# SBH_MCU.net
KiCad netlist of a schematic drawn in Altium Designer
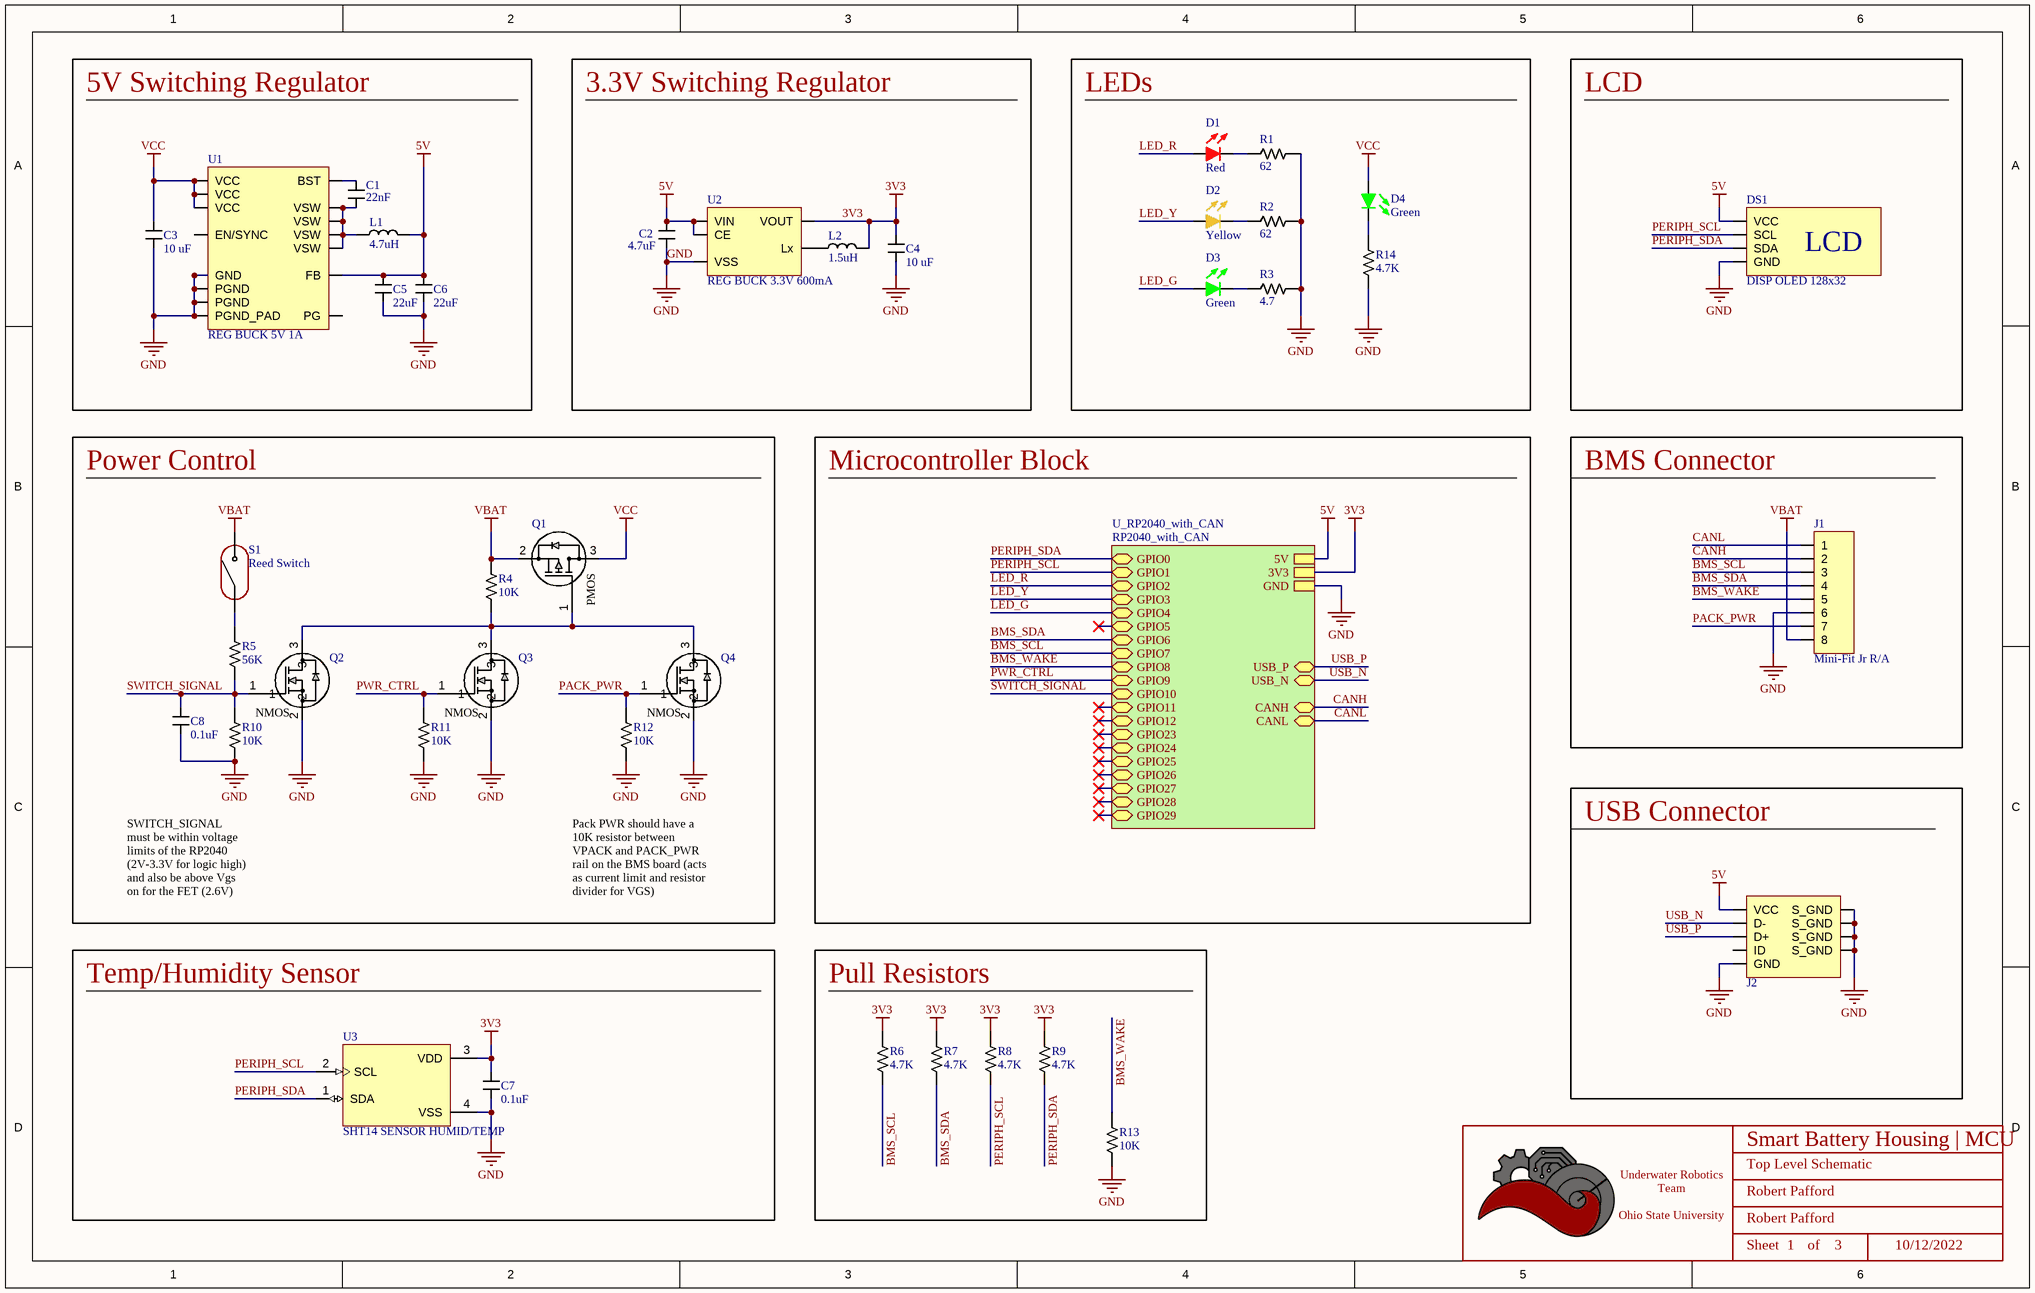
[diagram p0: SBH_MCU.SchDoc]

(export (version "E")
  (design (tool "Eeschema 10.0.6"))
  (components
    (comp (ref "*")
      (value "Title_Block")
      (footprint "LOGO")
      (description "UWRT Schematic Title Block Template\r\n\r\nCreated June 2021, Dylan Trainor")
      (libsource (lib "UWRT") (part "Title_Block"))
    )
    (comp (ref "C1")
      (value "22nF")
      (footprint "CAPACITOR_0402")
      (description "Cap 22nF 25V +/-10%\r\nCeramic 0402")
      (fields
        (field (name "TOLERANCE") "+/- 10%")
        (field (name "VOLTAGE") "25V")
        (field (name "MADE BY") "Robert Pafford")
      )
      (libsource (lib "Capacitors") (part "CAPACITOR_0.022uF_0402"))
    )
    (comp (ref "C2")
      (value "4.7uF")
      (footprint "CAPACITOR_0603")
      (description "Cap 4.7uF 6.3V +/-10%\r\nCeramic 0603")
      (fields
        (field (name "TOLERANCE") "+/- 10%")
        (field (name "VOLTAGE") "6.3V")
        (field (name "MADE BY") "Robert Pafford")
      )
      (libsource (lib "Capacitors") (part "CAPACITOR_4.7uF_0603"))
    )
    (comp (ref "C3")
      (value "10uF Ceramic 25V")
      (footprint "CAPACITOR_1206")
      (description "Cap 10uF 25V +/-10%\r\nCeramic 1206")
      (fields
        (field (name "TOLERANCE") "+/- 10%")
        (field (name "VOLTAGE") "25V")
        (field (name "VALUE (UF)") "10 uF")
        (field (name "MADE BY") "Robert Pafford")
      )
      (libsource (lib "Capacitors") (part "CAPACITOR_10uF_1206"))
    )
    (comp (ref "C4")
      (value "10uF Ceramic 6.3V")
      (footprint "CAPACITOR_0603")
      (description "Cap 10uF 6.3V +/-20%\r\nCeramic 0603")
      (fields
        (field (name "TOLERANCE") "+/- 20%")
        (field (name "VOLTAGE") "6.3V")
        (field (name "VALUE (UF)") "10 uF")
        (field (name "MADE BY") "Flip B")
      )
      (libsource (lib "Capacitors") (part "CAPACITOR_10uF_0603"))
    )
    (comp (ref "C5")
      (value "22uF")
      (footprint "CAPACITOR_0805")
      (description "Cap 22uF 10V +/-20% X5R\r\nCeramic 0805")
      (fields
        (field (name "TOLERANCE") "+/- 20%")
        (field (name "VOLTAGE") "10V")
        (field (name "MADE BY") "Robert Pafford")
      )
      (libsource (lib "Capacitors") (part "CAPACITOR_22uF_0805"))
    )
    (comp (ref "C6")
      (value "22uF")
      (footprint "CAPACITOR_0805")
      (description "Cap 22uF 10V +/-20% X5R\r\nCeramic 0805")
      (fields
        (field (name "TOLERANCE") "+/- 20%")
        (field (name "VOLTAGE") "10V")
        (field (name "MADE BY") "Robert Pafford")
      )
      (libsource (lib "Capacitors") (part "CAPACITOR_22uF_0805"))
    )
    (comp (ref "C7")
      (value "0.1uF")
      (footprint "CAPACITOR_0402")
      (description "Cap 100nF 25V +/-10%\r\nCeramic 0402")
      (fields
        (field (name "TOLERANCE") "+/- 10%")
        (field (name "VOLTAGE") "25V")
        (field (name "MADE BY") "Robert Pafford")
      )
      (libsource (lib "Capacitors") (part "CAPACITOR_0.1uF_0402"))
    )
    (comp (ref "C8")
      (value "0.1uF")
      (footprint "CAPACITOR_0402")
      (description "Cap 100nF 25V +/-10%\r\nCeramic 0402")
      (fields
        (field (name "TOLERANCE") "+/- 10%")
        (field (name "VOLTAGE") "25V")
        (field (name "MADE BY") "Robert Pafford")
      )
      (libsource (lib "Capacitors") (part "CAPACITOR_0.1uF_0402"))
    )
    (comp (ref "D1")
      (value "150060RS75000")
      (footprint "LED_0603")
      (description "LED Red Vf= 2V If = 0.020A\r\n150060RS75000")
      (fields (field (name "COLOR") "Red") (field (name "MADE BY") "Robert Pafford"))
      (libsource (lib "Diodes") (part "LED_Red_0603"))
    )
    (comp (ref "D2")
      (value "150060YS75000")
      (footprint "LED_0603")
      (description "LED Yellow Vf= 2V If = 0.020A\r\n150060YS75000")
      (fields (field (name "COLOR") "Yellow") (field (name "MADE BY") "Robert Pafford"))
      (libsource (lib "Diodes") (part "LED_Yellow_0603"))
    )
    (comp (ref "D3")
      (value "150060GS75000")
      (footprint "LED_0603")
      (description "LED Green Vf= 3.2V If = 0.025A\r\n150060GS75000")
      (fields (field (name "COLOR") "Green") (field (name "MADE BY") "Flip B"))
      (libsource (lib "Diodes") (part "LED_Green_0603_3.2V"))
    )
    (comp (ref "D4")
      (value "150060GS75000")
      (footprint "LED_0603")
      (description "LED Green Vf= 3.2V If = 0.025A\r\n150060GS75000")
      (fields (field (name "COLOR") "Green") (field (name "MADE BY") "Flip B"))
      (libsource (lib "Diodes") (part "LED_Green_0603_3.2V"))
    )
    (comp (ref "DS1")
      (value "DISP OLED 128x32")
      (footprint "OLED_I2C_128x32")
      (description "0.91'' 128x32 I2C OLED LCD Display Module")
      (fields (field (name "MADE BY") "Robert Pafford"))
      (libsource (lib "Modules") (part "OLED_I2C_128x32"))
    )
    (comp (ref "J1")
      (value "Mini-Fit Jr R/A")
      (footprint "Molex_Mili-Grid_2x4PIN_2.00MM_RA")
      (description "Molex Mili-Grid 2.00mm pitch 8 Pos Right Angle")
      (fields (field (name "MANUFACTURER") "Molex") (field (name "CREATED BY") "Flip B"))
      (libsource (lib "Connectors") (part "CONN_MOLEX_MiliGrid_8POS_R/A"))
    )
    (comp (ref "J2")
      (value "USB_MICRO R/A")
      (footprint "CONN_MINIUSB")
      (description "Amphenol Micro USB-B\r\nUSB2.0 5 Pin Right Angle SMD")
      (fields (field (name "MANUFACTURER") "Amphenol") (field (name "CREATED BY") "Flip B"))
      (libsource (lib "Connectors") (part "CONN_MICROUSB"))
    )
    (comp (ref "L1")
      (value "4.7uH")
      (footprint "INDUCTOR_SLF7045")
      (description "4.7 µH Shielded Drum Core, Wirewound Inductor 2.1 A 36mOhm Max Nonstandard")
      (fields
        (field (name "TOLERANCE") "+/- 20%")
        (field (name "Comment") "4.7uH Shielded Drum Core")
        (field (name "MADE BY") "Robert Pafford")
      )
      (libsource (lib "Inductors") (part "INDUCTOR_4.7uH_SLF7045T"))
    )
    (comp (ref "L2")
      (value "1.5uH")
      (footprint "INDUCTOR_NR3015")
      (description "Inductor Shielded 1.5uH 1.8A +/-30%")
      (fields
        (field (name "TOLERANCE") "+/- 30%")
        (field (name "Comment") "1.5uH Shielded")
        (field (name "MADE BY") "Robert Pafford")
      )
      (libsource (lib "Inductors") (part "INDUCTOR_1.5uH_NR3015"))
    )
    (comp (ref "Q1")
      (value "DMP3056L-7")
      (footprint "SOT-23-3")
      (description "P-Channel 30V 4.3A (Ta) 1.38W (Ta) Surface Mount SOT23")
      (fields (field (name "CREATED BY") "John Ulm") (field (name "REVIEWED BY") "---"))
      (libsource (lib "Transistors") (part "DMP3056L-7"))
    )
    (comp (ref "Q2")
      (value "MOSFET N-CH 30V 5.8A SOT-23-3")
      (footprint "SOT-23-3")
      (description "N-Channel 30 V 5.8A (Ta) 1.4W (Ta) Surface Mount SOT-23-3")
      (fields (field (name "MANUFACTURER _PART_NUMBER") "AO3404A") (field (name "CREATED BY") "Dylan T"))
      (libsource (lib "Transistors") (part "AO3404A"))
    )
    (comp (ref "Q3")
      (value "MOSFET N-CH 30V 5.8A SOT-23-3")
      (footprint "SOT-23-3")
      (description "N-Channel 30 V 5.8A (Ta) 1.4W (Ta) Surface Mount SOT-23-3")
      (fields (field (name "MANUFACTURER _PART_NUMBER") "AO3404A") (field (name "CREATED BY") "Dylan T"))
      (libsource (lib "Transistors") (part "AO3404A"))
    )
    (comp (ref "Q4")
      (value "MOSFET N-CH 30V 5.8A SOT-23-3")
      (footprint "SOT-23-3")
      (description "N-Channel 30 V 5.8A (Ta) 1.4W (Ta) Surface Mount SOT-23-3")
      (fields (field (name "MANUFACTURER _PART_NUMBER") "AO3404A") (field (name "CREATED BY") "Dylan T"))
      (libsource (lib "Transistors") (part "AO3404A"))
    )
    (comp (ref "R1")
      (value "62 Ohm 1% 1/4W")
      (footprint "RESISTOR_0603")
      (description "RES SMD 62 OHM 1% 1/4W 0603")
      (fields
        (field (name "TOLERANCE") "+/- 1%")
        (field (name "VALUE  (OHMS)") "62")
        (field (name "MADE BY") "Robert Pafford")
      )
      (libsource (lib "Resistors") (part "RESISTOR_62_0603"))
    )
    (comp (ref "R2")
      (value "62 Ohm 1% 1/4W")
      (footprint "RESISTOR_0603")
      (description "RES SMD 62 OHM 1% 1/4W 0603")
      (fields
        (field (name "TOLERANCE") "+/- 1%")
        (field (name "VALUE  (OHMS)") "62")
        (field (name "MADE BY") "Robert Pafford")
      )
      (libsource (lib "Resistors") (part "RESISTOR_62_0603"))
    )
    (comp (ref "R3")
      (value "4.7 Ohm 5% 1/8W")
      (footprint "RESISTOR_0603")
      (description "RES 4.7 OHM 5% 1/8W 0603")
      (fields
        (field (name "TOLERANCE") "+/- 5%")
        (field (name "VALUE  (OHMS)") "4.7")
        (field (name "MADE BY") "Robert Pafford")
      )
      (libsource (lib "Resistors") (part "RESISTOR_4.7_0603"))
    )
    (comp (ref "R4")
      (value "10k Ohm 5% 1/10W")
      (footprint "RESISTOR_0603")
      (description "RES 10k OHM 5% 1/10W 0603")
      (fields
        (field (name "TOLERANCE") "+/- 5%")
        (field (name "VALUE  (OHMS)") "10K")
        (field (name "MADE BY") "Robert Pafford")
      )
      (libsource (lib "Resistors") (part "RESISTOR_10K_0603"))
    )
    (comp (ref "R5")
      (value "56k Ohm 1% 1/16W")
      (footprint "RESISTOR_0402")
      (description "RES 56k OHM 1% 1/16W 0402")
      (fields
        (field (name "TOLERANCE") "+/- 1%")
        (field (name "VALUE  (OHMS)") "56K")
        (field (name "MADE BY") "Robert Pafford")
      )
      (libsource (lib "Resistors") (part "RESISTOR_56K_0402"))
    )
    (comp (ref "R6")
      (value "4.7k Ohm 5% 1/10W")
      (footprint "RESISTOR_0603")
      (description "RES 4.7k OHM 5% 1/10W 0603")
      (fields
        (field (name "TOLERANCE") "+/- 5%")
        (field (name "VALUE  (OHMS)") "4.7K")
        (field (name "MADE BY") "Robert Pafford")
      )
      (libsource (lib "Resistors") (part "RESISTOR_4.7K_0603"))
    )
    (comp (ref "R7")
      (value "4.7k Ohm 5% 1/10W")
      (footprint "RESISTOR_0603")
      (description "RES 4.7k OHM 5% 1/10W 0603")
      (fields
        (field (name "TOLERANCE") "+/- 5%")
        (field (name "VALUE  (OHMS)") "4.7K")
        (field (name "MADE BY") "Robert Pafford")
      )
      (libsource (lib "Resistors") (part "RESISTOR_4.7K_0603"))
    )
    (comp (ref "R8")
      (value "4.7k Ohm 5% 1/10W")
      (footprint "RESISTOR_0603")
      (description "RES 4.7k OHM 5% 1/10W 0603")
      (fields
        (field (name "TOLERANCE") "+/- 5%")
        (field (name "VALUE  (OHMS)") "4.7K")
        (field (name "MADE BY") "Robert Pafford")
      )
      (libsource (lib "Resistors") (part "RESISTOR_4.7K_0603"))
    )
    (comp (ref "R9")
      (value "4.7k Ohm 5% 1/10W")
      (footprint "RESISTOR_0603")
      (description "RES 4.7k OHM 5% 1/10W 0603")
      (fields
        (field (name "TOLERANCE") "+/- 5%")
        (field (name "VALUE  (OHMS)") "4.7K")
        (field (name "MADE BY") "Robert Pafford")
      )
      (libsource (lib "Resistors") (part "RESISTOR_4.7K_0603"))
    )
    (comp (ref "R10")
      (value "10k Ohm 5% 1/10W")
      (footprint "RESISTOR_0603")
      (description "RES 10k OHM 5% 1/10W 0603")
      (fields
        (field (name "TOLERANCE") "+/- 5%")
        (field (name "VALUE  (OHMS)") "10K")
        (field (name "MADE BY") "Robert Pafford")
      )
      (libsource (lib "Resistors") (part "RESISTOR_10K_0603"))
    )
    (comp (ref "R11")
      (value "10k Ohm 5% 1/10W")
      (footprint "RESISTOR_0603")
      (description "RES 10k OHM 5% 1/10W 0603")
      (fields
        (field (name "TOLERANCE") "+/- 5%")
        (field (name "VALUE  (OHMS)") "10K")
        (field (name "MADE BY") "Robert Pafford")
      )
      (libsource (lib "Resistors") (part "RESISTOR_10K_0603"))
    )
    (comp (ref "R12")
      (value "10k Ohm 5% 1/10W")
      (footprint "RESISTOR_0603")
      (description "RES 10k OHM 5% 1/10W 0603")
      (fields
        (field (name "TOLERANCE") "+/- 5%")
        (field (name "VALUE  (OHMS)") "10K")
        (field (name "MADE BY") "Robert Pafford")
      )
      (libsource (lib "Resistors") (part "RESISTOR_10K_0603"))
    )
    (comp (ref "R13")
      (value "10k Ohm 5% 1/10W")
      (footprint "RESISTOR_0603")
      (description "RES 10k OHM 5% 1/10W 0603")
      (fields
        (field (name "TOLERANCE") "+/- 5%")
        (field (name "VALUE  (OHMS)") "10K")
        (field (name "MADE BY") "Robert Pafford")
      )
      (libsource (lib "Resistors") (part "RESISTOR_10K_0603"))
    )
    (comp (ref "R14")
      (value "4.7k Ohm 5% 1/10W")
      (footprint "RESISTOR_0603")
      (description "RES 4.7k OHM 5% 1/10W 0603")
      (fields
        (field (name "TOLERANCE") "+/- 5%")
        (field (name "VALUE  (OHMS)") "4.7K")
        (field (name "MADE BY") "Robert Pafford")
      )
      (libsource (lib "Resistors") (part "RESISTOR_4.7K_0603"))
    )
    (comp (ref "S1")
      (value "Reed Switch")
      (footprint "MDSR-7")
      (fields (field (name "MADE BY") "Robert Pafford"))
      (libsource (lib "Switches") (part "Reed Switch"))
    )
    (comp (ref "U1")
      (value "REG BUCK 5V 1A")
      (footprint "QFN-16 (3x3)")
      (description "Buck Switching Regulator IC Positive Fixed 5V 1 Output 1A 16-VFQFN Exposed Pad")
      (fields (field (name "MADE BY") "Robert Pafford"))
      (libsource (lib "Integrated Circuits") (part "TS30041-M050QFNR"))
    )
    (comp (ref "U2")
      (value "REG BUCK 3.3V 600mA")
      (footprint "SOT-23-5")
      (description "Buck Switching Regulator IC Positive Fixed 3.3V 1 Output 600mA SOT25")
      (fields (field (name "MADE BY") "Robert Pafford"))
      (libsource (lib "Integrated Circuits") (part "XC9236A33DMR-G"))
    )
    (comp (ref "U3")
      (value "SHT14 SENSOR HUMID/TEMP")
      (footprint "XDCR_SHT41-AD1B-R2")
      (description "Digital Relative Humidity Temperature Sensor, Â±1.8 / max 2.5 %RH, Â±0.2 Â°C, Ultra-Low-Power")
      (fields (field (name "MP") "SHT41-AD1B-R2") (field (name "MF") "Sensirion"))
      (libsource (lib "Integrated Circuits") (part "SHT41-AD1B-R2"))
    )
  )
  (nets
    (net (code "1") (name "/BMS_SCL") (class "Default")
      (node (ref "J1") (pin "3") (pinfunction "3_3") (pintype "passive"))
      (node (ref "R6") (pin "2") (pinfunction "2_2") (pintype "passive"))
    )
    (net (code "2") (name "/BMS_SDA") (class "Default")
      (node (ref "J1") (pin "4") (pinfunction "4_4") (pintype "passive"))
      (node (ref "R7") (pin "2") (pinfunction "2_2") (pintype "passive"))
    )
    (net (code "3") (name "/BMS_WAKE") (class "Default")
      (node (ref "J1") (pin "5") (pinfunction "5_5") (pintype "passive"))
      (node (ref "R13") (pin "1") (pinfunction "1_1") (pintype "passive"))
    )
    (net (code "4") (name "/CANH") (class "Default")
      (node (ref "J1") (pin "2") (pinfunction "2_2") (pintype "passive"))
    )
    (net (code "5") (name "/CANL") (class "Default")
      (node (ref "J1") (pin "1") (pinfunction "1_1") (pintype "passive"))
    )
    (net (code "16") (name "/LED_G") (class "Default")
      (node (ref "D3") (pin "1") (pinfunction "1_1") (pintype "passive"))
    )
    (net (code "17") (name "/LED_R") (class "Default")
      (node (ref "D1") (pin "1") (pinfunction "1_1") (pintype "passive"))
    )
    (net (code "18") (name "/LED_Y") (class "Default")
      (node (ref "D2") (pin "1") (pinfunction "1_1") (pintype "passive"))
    )
    (net (code "19") (name "/PACK_PWR") (class "Default")
      (node (ref "J1") (pin "7") (pinfunction "7_7") (pintype "passive"))
      (node (ref "Q4") (pin "1") (pinfunction "1_1") (pintype "passive"))
      (node (ref "R12") (pin "1") (pinfunction "1_1") (pintype "passive"))
    )
    (net (code "20") (name "/PERIPH_SCL") (class "Default")
      (node (ref "DS1") (pin "3") (pinfunction "SCL_3") (pintype "passive"))
      (node (ref "R8") (pin "2") (pinfunction "2_2") (pintype "passive"))
      (node (ref "U3") (pin "2") (pinfunction "SCL_2") (pintype "input"))
    )
    (net (code "21") (name "/PERIPH_SDA") (class "Default")
      (node (ref "DS1") (pin "4") (pinfunction "SDA_4") (pintype "passive"))
      (node (ref "R9") (pin "2") (pinfunction "2_2") (pintype "passive"))
      (node (ref "U3") (pin "1") (pinfunction "SDA_1") (pintype "bidirectional"))
    )
    (net (code "22") (name "/PWR_CTRL") (class "Default")
      (node (ref "Q3") (pin "1") (pinfunction "1_1") (pintype "passive"))
      (node (ref "R11") (pin "1") (pinfunction "1_1") (pintype "passive"))
    )
    (net (code "23") (name "/SWITCH_SIGNAL") (class "Default")
      (node (ref "C8") (pin "1") (pinfunction "1_1") (pintype "passive"))
      (node (ref "Q2") (pin "1") (pinfunction "1_1") (pintype "passive"))
      (node (ref "R10") (pin "1") (pinfunction "1_1") (pintype "passive"))
      (node (ref "R5") (pin "2") (pinfunction "2_2") (pintype "passive"))
    )
    (net (code "24") (name "/USB_N") (class "Default")
      (node (ref "J2") (pin "2") (pinfunction "D-_2") (pintype "passive"))
    )
    (net (code "25") (name "/USB_P") (class "Default")
      (node (ref "J2") (pin "3") (pinfunction "D+_3") (pintype "passive"))
    )
    (net (code "26") (name "3V3") (class "Default")
      (node (ref "C4") (pin "1") (pinfunction "1_1") (pintype "passive"))
      (node (ref "C7") (pin "1") (pinfunction "1_1") (pintype "passive"))
      (node (ref "L2") (pin "1") (pinfunction "1_1") (pintype "passive"))
      (node (ref "R6") (pin "1") (pinfunction "1_1") (pintype "passive"))
      (node (ref "R7") (pin "1") (pinfunction "1_1") (pintype "passive"))
      (node (ref "R8") (pin "1") (pinfunction "1_1") (pintype "passive"))
      (node (ref "R9") (pin "1") (pinfunction "1_1") (pintype "passive"))
      (node (ref "U2") (pin "4") (pinfunction "VOUT_4") (pintype "passive"))
      (node (ref "U3") (pin "3") (pinfunction "VDD_3") (pintype "power_in"))
    )
    (net (code "27") (name "5V") (class "Default")
      (node (ref "C2") (pin "1") (pinfunction "1_1") (pintype "passive"))
      (node (ref "C5") (pin "1") (pinfunction "1_1") (pintype "passive"))
      (node (ref "C6") (pin "1") (pinfunction "1_1") (pintype "passive"))
      (node (ref "DS1") (pin "2") (pinfunction "VCC_2") (pintype "passive"))
      (node (ref "J2") (pin "1") (pinfunction "VCC_1") (pintype "passive"))
      (node (ref "L1") (pin "1") (pinfunction "1_1") (pintype "passive"))
      (node (ref "U1") (pin "5") (pinfunction "FB_5") (pintype "passive"))
      (node (ref "U2") (pin "1") (pinfunction "VIN_1") (pintype "passive"))
      (node (ref "U2") (pin "3") (pinfunction "CE_3") (pintype "passive"))
    )
    (net (code "28") (name "GND") (class "Default")
      (node (ref "C2") (pin "2") (pinfunction "2_2") (pintype "passive"))
      (node (ref "C3") (pin "2") (pinfunction "2_2") (pintype "passive"))
      (node (ref "C4") (pin "2") (pinfunction "2_2") (pintype "passive"))
      (node (ref "C5") (pin "2") (pinfunction "2_2") (pintype "passive"))
      (node (ref "C6") (pin "2") (pinfunction "2_2") (pintype "passive"))
      (node (ref "C7") (pin "2") (pinfunction "2_2") (pintype "passive"))
      (node (ref "C8") (pin "2") (pinfunction "2_2") (pintype "passive"))
      (node (ref "DS1") (pin "1") (pinfunction "GND_1") (pintype "passive"))
      (node (ref "J1") (pin "6") (pinfunction "6_6") (pintype "passive"))
      (node (ref "J2") (pin "5") (pinfunction "GND_5") (pintype "passive"))
      (node (ref "J2") (pin "6") (pinfunction "S_GND_6") (pintype "passive"))
      (node (ref "J2") (pin "7") (pinfunction "S_GND_7") (pintype "passive"))
      (node (ref "J2") (pin "8") (pinfunction "S_GND_8") (pintype "passive"))
      (node (ref "J2") (pin "9") (pinfunction "S_GND_9") (pintype "passive"))
      (node (ref "Q2") (pin "2") (pinfunction "2_2") (pintype "passive"))
      (node (ref "Q3") (pin "2") (pinfunction "2_2") (pintype "passive"))
      (node (ref "Q4") (pin "2") (pinfunction "2_2") (pintype "passive"))
      (node (ref "R1") (pin "1") (pinfunction "1_1") (pintype "passive"))
      (node (ref "R10") (pin "2") (pinfunction "2_2") (pintype "passive"))
      (node (ref "R11") (pin "2") (pinfunction "2_2") (pintype "passive"))
      (node (ref "R12") (pin "2") (pinfunction "2_2") (pintype "passive"))
      (node (ref "R13") (pin "2") (pinfunction "2_2") (pintype "passive"))
      (node (ref "R14") (pin "2") (pinfunction "2_2") (pintype "passive"))
      (node (ref "R2") (pin "1") (pinfunction "1_1") (pintype "passive"))
      (node (ref "R3") (pin "1") (pinfunction "1_1") (pintype "passive"))
      (node (ref "U1") (pin "14") (pinfunction "PGND_14") (pintype "power_in"))
      (node (ref "U1") (pin "15") (pinfunction "PGND_15") (pintype "power_in"))
      (node (ref "U1") (pin "17") (pinfunction "PGND_PAD_17") (pintype "power_in"))
      (node (ref "U1") (pin "4") (pinfunction "GND_4") (pintype "power_in"))
      (node (ref "U2") (pin "2") (pinfunction "VSS_2") (pintype "passive"))
      (node (ref "U3") (pin "4") (pinfunction "VSS_4") (pintype "power_in"))
    )
    (net (code "29") (name "Net-(C1-Pad2)") (class "Default")
      (node (ref "C1") (pin "2") (pinfunction "2_2") (pintype "passive"))
      (node (ref "L1") (pin "2") (pinfunction "2_2") (pintype "passive"))
      (node (ref "U1") (pin "1") (pinfunction "VSW_1") (pintype "power_in"))
      (node (ref "U1") (pin "12") (pinfunction "VSW_12") (pintype "power_in"))
      (node (ref "U1") (pin "13") (pinfunction "VSW_13") (pintype "power_in"))
      (node (ref "U1") (pin "16") (pinfunction "VSW_16") (pintype "passive"))
    )
    (net (code "30") (name "Net-(D1-Pad2)") (class "Default")
      (node (ref "D1") (pin "2") (pinfunction "2_2") (pintype "passive"))
      (node (ref "R1") (pin "2") (pinfunction "2_2") (pintype "passive"))
    )
    (net (code "31") (name "Net-(D2-Pad2)") (class "Default")
      (node (ref "D2") (pin "2") (pinfunction "2_2") (pintype "passive"))
      (node (ref "R2") (pin "2") (pinfunction "2_2") (pintype "passive"))
    )
    (net (code "32") (name "Net-(D3-Pad2)") (class "Default")
      (node (ref "D3") (pin "2") (pinfunction "2_2") (pintype "passive"))
      (node (ref "R3") (pin "2") (pinfunction "2_2") (pintype "passive"))
    )
    (net (code "33") (name "Net-(D4-Pad2)") (class "Default")
      (node (ref "D4") (pin "2") (pinfunction "2_2") (pintype "passive"))
      (node (ref "R14") (pin "1") (pinfunction "1_1") (pintype "passive"))
    )
    (net (code "34") (name "Net-(Q1-Pad1)") (class "Default")
      (node (ref "Q1") (pin "1") (pinfunction "1_1") (pintype "passive"))
      (node (ref "Q2") (pin "3") (pinfunction "3_3") (pintype "passive"))
      (node (ref "Q3") (pin "3") (pinfunction "3_3") (pintype "passive"))
      (node (ref "Q4") (pin "3") (pinfunction "3_3") (pintype "passive"))
      (node (ref "R4") (pin "2") (pinfunction "2_2") (pintype "passive"))
    )
    (net (code "35") (name "Net-(R5-Pad1)") (class "Default")
      (node (ref "R5") (pin "1") (pinfunction "1_1") (pintype "passive"))
      (node (ref "S1") (pin "1") (pintype "passive"))
    )
    (net (code "36") (name "Net-(U1-BST)") (class "Default")
      (node (ref "C1") (pin "1") (pinfunction "1_1") (pintype "passive"))
      (node (ref "U1") (pin "10") (pinfunction "BST_10") (pintype "passive"))
    )
    (net (code "37") (name "Net-(U2-Lx)") (class "Default")
      (node (ref "L2") (pin "2") (pinfunction "2_2") (pintype "passive"))
      (node (ref "U2") (pin "5") (pinfunction "Lx_5") (pintype "passive"))
    )
    (net (code "38") (name "VBAT") (class "Default")
      (node (ref "J1") (pin "8") (pinfunction "8_8") (pintype "passive"))
      (node (ref "Q1") (pin "2") (pinfunction "2_2") (pintype "passive"))
      (node (ref "R4") (pin "1") (pinfunction "1_1") (pintype "passive"))
      (node (ref "S1") (pin "2") (pintype "passive"))
    )
    (net (code "39") (name "VCC") (class "Default")
      (node (ref "C3") (pin "1") (pinfunction "1_1") (pintype "passive"))
      (node (ref "D4") (pin "1") (pinfunction "1_1") (pintype "passive"))
      (node (ref "Q1") (pin "3") (pinfunction "3_3") (pintype "passive"))
      (node (ref "U1") (pin "11") (pinfunction "VCC_11") (pintype "power_in"))
      (node (ref "U1") (pin "2") (pinfunction "VCC_2") (pintype "power_in"))
      (node (ref "U1") (pin "3") (pinfunction "VCC_3") (pintype "power_in"))
    )
    (net (code "40") (name "unconnected-(J2-ID-Pad4)") (class "Default")
      (node (ref "J2") (pin "4") (pinfunction "ID_4") (pintype "passive"))
    )
    (net (code "41") (name "unconnected-(U1-EN{slash}SYNC-Pad9)") (class "Default")
      (node (ref "U1") (pin "9") (pinfunction "EN/SYNC_9") (pintype "passive"))
    )
    (net (code "42") (name "unconnected-(U1-PG-Pad8)") (class "Default")
      (node (ref "U1") (pin "8") (pinfunction "PG_8") (pintype "passive"))
    )
  )
)
